# mcu.net
KiCad netlist of a schematic drawn in Altium Designer
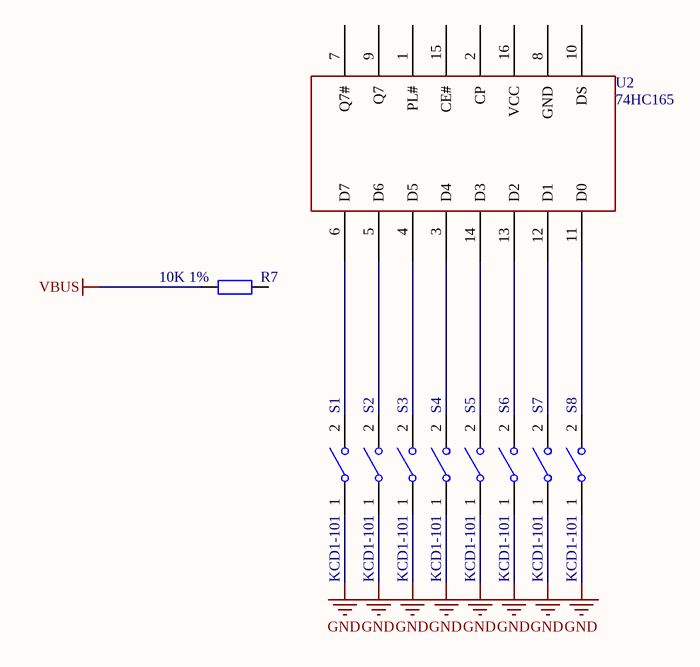
[diagram p0: mcu.SchDoc]

(export (version "E")
  (design (tool "Eeschema 10.0.6"))
  (components
    (comp (ref "R7")
      (value "10K 1%")
      (footprint "R0402_L")
      (description "贴片电阻")
      (fields (field (name "版权归属") "源创客"))
      (libsource (lib "Resistor") (part "R"))
    )
    (comp (ref "S1")
      (value "KCD1-101")
      (footprint "KCD1-101")
      (description "1路单刀船型开关")
      (fields (field (name "版权归属") "源创客"))
      (libsource (lib "Switch") (part "KCD1-101"))
    )
    (comp (ref "S2")
      (value "KCD1-101")
      (footprint "KCD1-101")
      (description "1路单刀船型开关")
      (fields (field (name "版权归属") "源创客"))
      (libsource (lib "Switch") (part "KCD1-101"))
    )
    (comp (ref "S3")
      (value "KCD1-101")
      (footprint "KCD1-101")
      (description "1路单刀船型开关")
      (fields (field (name "版权归属") "源创客"))
      (libsource (lib "Switch") (part "KCD1-101"))
    )
    (comp (ref "S4")
      (value "KCD1-101")
      (footprint "KCD1-101")
      (description "1路单刀船型开关")
      (fields (field (name "版权归属") "源创客"))
      (libsource (lib "Switch") (part "KCD1-101"))
    )
    (comp (ref "S5")
      (value "KCD1-101")
      (footprint "KCD1-101")
      (description "1路单刀船型开关")
      (fields (field (name "版权归属") "源创客"))
      (libsource (lib "Switch") (part "KCD1-101"))
    )
    (comp (ref "S6")
      (value "KCD1-101")
      (footprint "KCD1-101")
      (description "1路单刀船型开关")
      (fields (field (name "版权归属") "源创客"))
      (libsource (lib "Switch") (part "KCD1-101"))
    )
    (comp (ref "S7")
      (value "KCD1-101")
      (footprint "KCD1-101")
      (description "1路单刀船型开关")
      (fields (field (name "版权归属") "源创客"))
      (libsource (lib "Switch") (part "KCD1-101"))
    )
    (comp (ref "S8")
      (value "KCD1-101")
      (footprint "KCD1-101")
      (description "1路单刀船型开关")
      (fields (field (name "版权归属") "源创客"))
      (libsource (lib "Switch") (part "KCD1-101"))
    )
    (comp (ref "U2")
      (value "74HC165")
      (footprint "SOP16_L")
      (description "移位寄存器")
      (libsource (lib "移位寄存器") (part "74HC165"))
    )
  )
  (nets
    (net (code "1") (name "GND") (class "Default")
      (node (ref "S1") (pin "1") (pinfunction "1_1") (pintype "passive"))
      (node (ref "S2") (pin "1") (pinfunction "1_1") (pintype "passive"))
      (node (ref "S3") (pin "1") (pinfunction "1_1") (pintype "passive"))
      (node (ref "S4") (pin "1") (pinfunction "1_1") (pintype "passive"))
      (node (ref "S5") (pin "1") (pinfunction "1_1") (pintype "passive"))
      (node (ref "S6") (pin "1") (pinfunction "1_1") (pintype "passive"))
      (node (ref "S7") (pin "1") (pinfunction "1_1") (pintype "passive"))
      (node (ref "S8") (pin "1") (pinfunction "1_1") (pintype "passive"))
    )
    (net (code "2") (name "Net-(U2-D0)") (class "Default")
      (node (ref "S8") (pin "2") (pinfunction "2_2") (pintype "passive"))
      (node (ref "U2") (pin "11") (pinfunction "D0_11") (pintype "passive"))
    )
    (net (code "3") (name "Net-(U2-D1)") (class "Default")
      (node (ref "S7") (pin "2") (pinfunction "2_2") (pintype "passive"))
      (node (ref "U2") (pin "12") (pinfunction "D1_12") (pintype "passive"))
    )
    (net (code "4") (name "Net-(U2-D2)") (class "Default")
      (node (ref "S6") (pin "2") (pinfunction "2_2") (pintype "passive"))
      (node (ref "U2") (pin "13") (pinfunction "D2_13") (pintype "passive"))
    )
    (net (code "5") (name "Net-(U2-D3)") (class "Default")
      (node (ref "S5") (pin "2") (pinfunction "2_2") (pintype "passive"))
      (node (ref "U2") (pin "14") (pinfunction "D3_14") (pintype "passive"))
    )
    (net (code "6") (name "Net-(U2-D4)") (class "Default")
      (node (ref "S4") (pin "2") (pinfunction "2_2") (pintype "passive"))
      (node (ref "U2") (pin "3") (pinfunction "D4_3") (pintype "passive"))
    )
    (net (code "7") (name "Net-(U2-D5)") (class "Default")
      (node (ref "S3") (pin "2") (pinfunction "2_2") (pintype "passive"))
      (node (ref "U2") (pin "4") (pinfunction "D5_4") (pintype "passive"))
    )
    (net (code "8") (name "Net-(U2-D6)") (class "Default")
      (node (ref "S2") (pin "2") (pinfunction "2_2") (pintype "passive"))
      (node (ref "U2") (pin "5") (pinfunction "D6_5") (pintype "passive"))
    )
    (net (code "9") (name "Net-(U2-D7)") (class "Default")
      (node (ref "S1") (pin "2") (pinfunction "2_2") (pintype "passive"))
      (node (ref "U2") (pin "6") (pinfunction "D7_6") (pintype "passive"))
    )
    (net (code "10") (name "VBUS") (class "Default")
      (node (ref "R7") (pin "1") (pinfunction "1_1") (pintype "passive"))
    )
    (net (code "11") (name "unconnected-(R7-Pad2)") (class "Default")
      (node (ref "R7") (pin "2") (pinfunction "2_2") (pintype "passive"))
    )
    (net (code "12") (name "unconnected-(U2-CE#-Pad15)") (class "Default")
      (node (ref "U2") (pin "15") (pinfunction "CE#_15") (pintype "passive"))
    )
    (net (code "13") (name "unconnected-(U2-CP-Pad2)") (class "Default")
      (node (ref "U2") (pin "2") (pinfunction "CP_2") (pintype "passive"))
    )
    (net (code "14") (name "unconnected-(U2-DS-Pad10)") (class "Default")
      (node (ref "U2") (pin "10") (pinfunction "DS_10") (pintype "passive"))
    )
    (net (code "15") (name "unconnected-(U2-GND-Pad8)") (class "Default")
      (node (ref "U2") (pin "8") (pinfunction "GND_8") (pintype "passive"))
    )
    (net (code "16") (name "unconnected-(U2-PL#-Pad1)") (class "Default")
      (node (ref "U2") (pin "1") (pinfunction "PL#_1") (pintype "passive"))
    )
    (net (code "17") (name "unconnected-(U2-Q7#-Pad7)") (class "Default")
      (node (ref "U2") (pin "7") (pinfunction "Q7#_7") (pintype "passive"))
    )
    (net (code "18") (name "unconnected-(U2-Q7-Pad9)") (class "Default")
      (node (ref "U2") (pin "9") (pinfunction "Q7_9") (pintype "passive"))
    )
    (net (code "19") (name "unconnected-(U2-VCC-Pad16)") (class "Default")
      (node (ref "U2") (pin "16") (pinfunction "VCC_16") (pintype "passive"))
    )
  )
)
